# Rocket-Switch-Interface-ProtoBoard.net
KiCad netlist of a schematic drawn in EAGLE
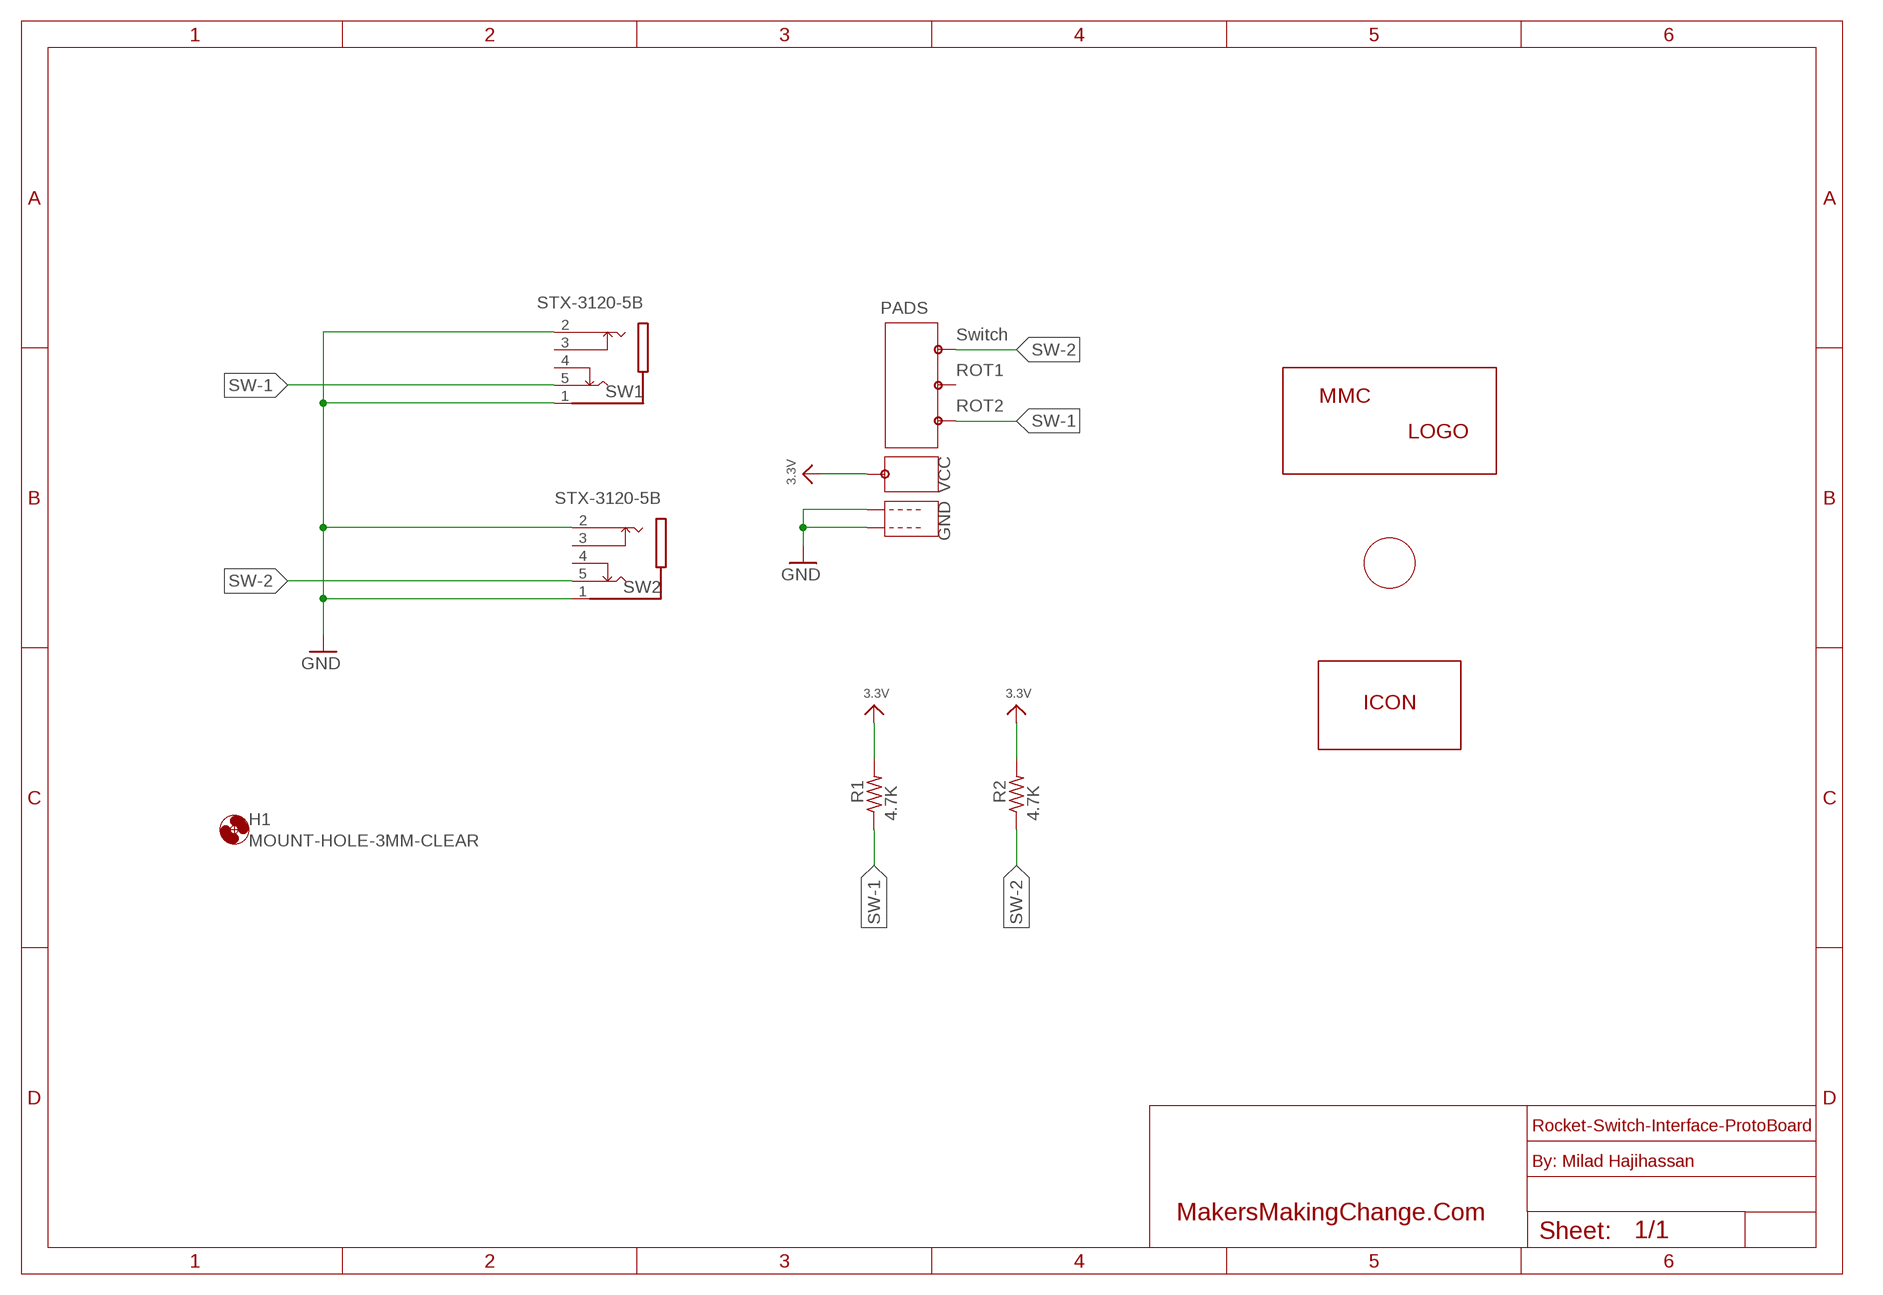
[diagram p0: schematic, sheet 1]

(export (version "E")
  (design (tool "Eeschema 10.0.6"))
  (components
    (comp (ref "H1")
      (value "MOUNT-HOLE-3MM-CLEAR")
      (footprint "eagle-import:HOLE-3MM-CLEAR")
      (libsource (lib "eagle-import") (part "MOUNT-HOLE-3MM-CLEAR"))
    )
    (comp (ref "LABEL_BACKGROUND")
      (value "MMC_ICON-ROCKET-SW")
      (footprint "eagle-import:ICON_ROCKET-SWITCH")
      (libsource (lib "eagle-import") (part "MMC_ICON-ROCKET-SW"))
    )
    (comp (ref "LABEL_DEVICE")
      (value "MMC_LABEL-ROCKET-SW")
      (footprint "eagle-import:LABEL-ROCKET-SWITCH")
      (libsource (lib "eagle-import") (part "MMC_LABEL-ROCKET-SW"))
    )
    (comp (ref "LABEL_LOGO")
      (value "MMC_LOGO-XSM")
      (footprint "eagle-import:MMC_X-SMALL_LOGO")
      (libsource (lib "eagle-import") (part "MMC_LOGO-XSM"))
    )
    (comp (ref "PADS")
      (value "PADS-ROTARY-TRINKEY")
      (footprint "eagle-import:PADS-ROTARY-TRINKEY")
      (libsource (lib "eagle-import") (part "PADS-ROTARY-TRINKEY"))
    )
    (comp (ref "R1")
      (value "4.7K")
      (footprint "eagle-import:RESISTOR_0204_5")
      (libsource (lib "eagle-import") (part "RESISTOR-US-0204/5"))
    )
    (comp (ref "R2")
      (value "4.7K")
      (footprint "eagle-import:RESISTOR_0204_5")
      (libsource (lib "eagle-import") (part "RESISTOR-US-0204/5"))
    )
    (comp (ref "SW1")
      (value "STX-3120-5B")
      (footprint "eagle-import:STX-3120-5B")
      (libsource (lib "eagle-import") (part "STX-3120-5B"))
    )
    (comp (ref "SW2")
      (value "STX-3120-5B")
      (footprint "eagle-import:STX-3120-5B")
      (libsource (lib "eagle-import") (part "STX-3120-5B"))
    )
  )
  (nets
    (net (code "1") (name "3.3V") (class "Default")
      (node (ref "PADS") (pin "P$VCC") (pinfunction "P$VCC_P$VCC") (pintype "passive"))
      (node (ref "R1") (pin "2") (pinfunction "2_2") (pintype "passive"))
      (node (ref "R2") (pin "2") (pinfunction "2_2") (pintype "passive"))
    )
    (net (code "2") (name "GND") (class "Default")
      (node (ref "PADS") (pin "P$GND1") (pinfunction "P$GND1_P$GND1") (pintype "passive"))
      (node (ref "PADS") (pin "P$GND2") (pinfunction "P$GND2_P$GND2") (pintype "passive"))
      (node (ref "SW1") (pin "1") (pinfunction "1_1") (pintype "passive"))
      (node (ref "SW1") (pin "2") (pinfunction "2_2") (pintype "passive"))
      (node (ref "SW2") (pin "1") (pinfunction "1_1") (pintype "passive"))
      (node (ref "SW2") (pin "2") (pinfunction "2_2") (pintype "passive"))
    )
    (net (code "3") (name "SW-1") (class "Default")
      (node (ref "PADS") (pin "P$ROT2") (pinfunction "P$ROT2_P$ROT2") (pintype "passive"))
      (node (ref "R1") (pin "1") (pinfunction "1_1") (pintype "passive"))
      (node (ref "SW1") (pin "5") (pinfunction "5_5") (pintype "passive"))
    )
    (net (code "4") (name "SW-2") (class "Default")
      (node (ref "PADS") (pin "P$SW") (pinfunction "P$SW_P$SW") (pintype "passive"))
      (node (ref "R2") (pin "1") (pinfunction "1_1") (pintype "passive"))
      (node (ref "SW2") (pin "5") (pinfunction "5_5") (pintype "passive"))
    )
    (net (code "5") (name "unconnected-(PADS-PadP$ROT1)") (class "Default")
      (node (ref "PADS") (pin "P$ROT1") (pinfunction "P$ROT1_P$ROT1") (pintype "passive"))
    )
    (net (code "6") (name "unconnected-(SW1-Pad3)") (class "Default")
      (node (ref "SW1") (pin "3") (pinfunction "3_3") (pintype "passive"))
    )
    (net (code "7") (name "unconnected-(SW1-Pad4)") (class "Default")
      (node (ref "SW1") (pin "4") (pinfunction "4_4") (pintype "passive"))
    )
    (net (code "8") (name "unconnected-(SW2-Pad3)") (class "Default")
      (node (ref "SW2") (pin "3") (pinfunction "3_3") (pintype "passive"))
    )
    (net (code "9") (name "unconnected-(SW2-Pad4)") (class "Default")
      (node (ref "SW2") (pin "4") (pinfunction "4_4") (pintype "passive"))
    )
  )
)
